# charliewatch-0402.net
KiCad netlist of a schematic drawn in EAGLE
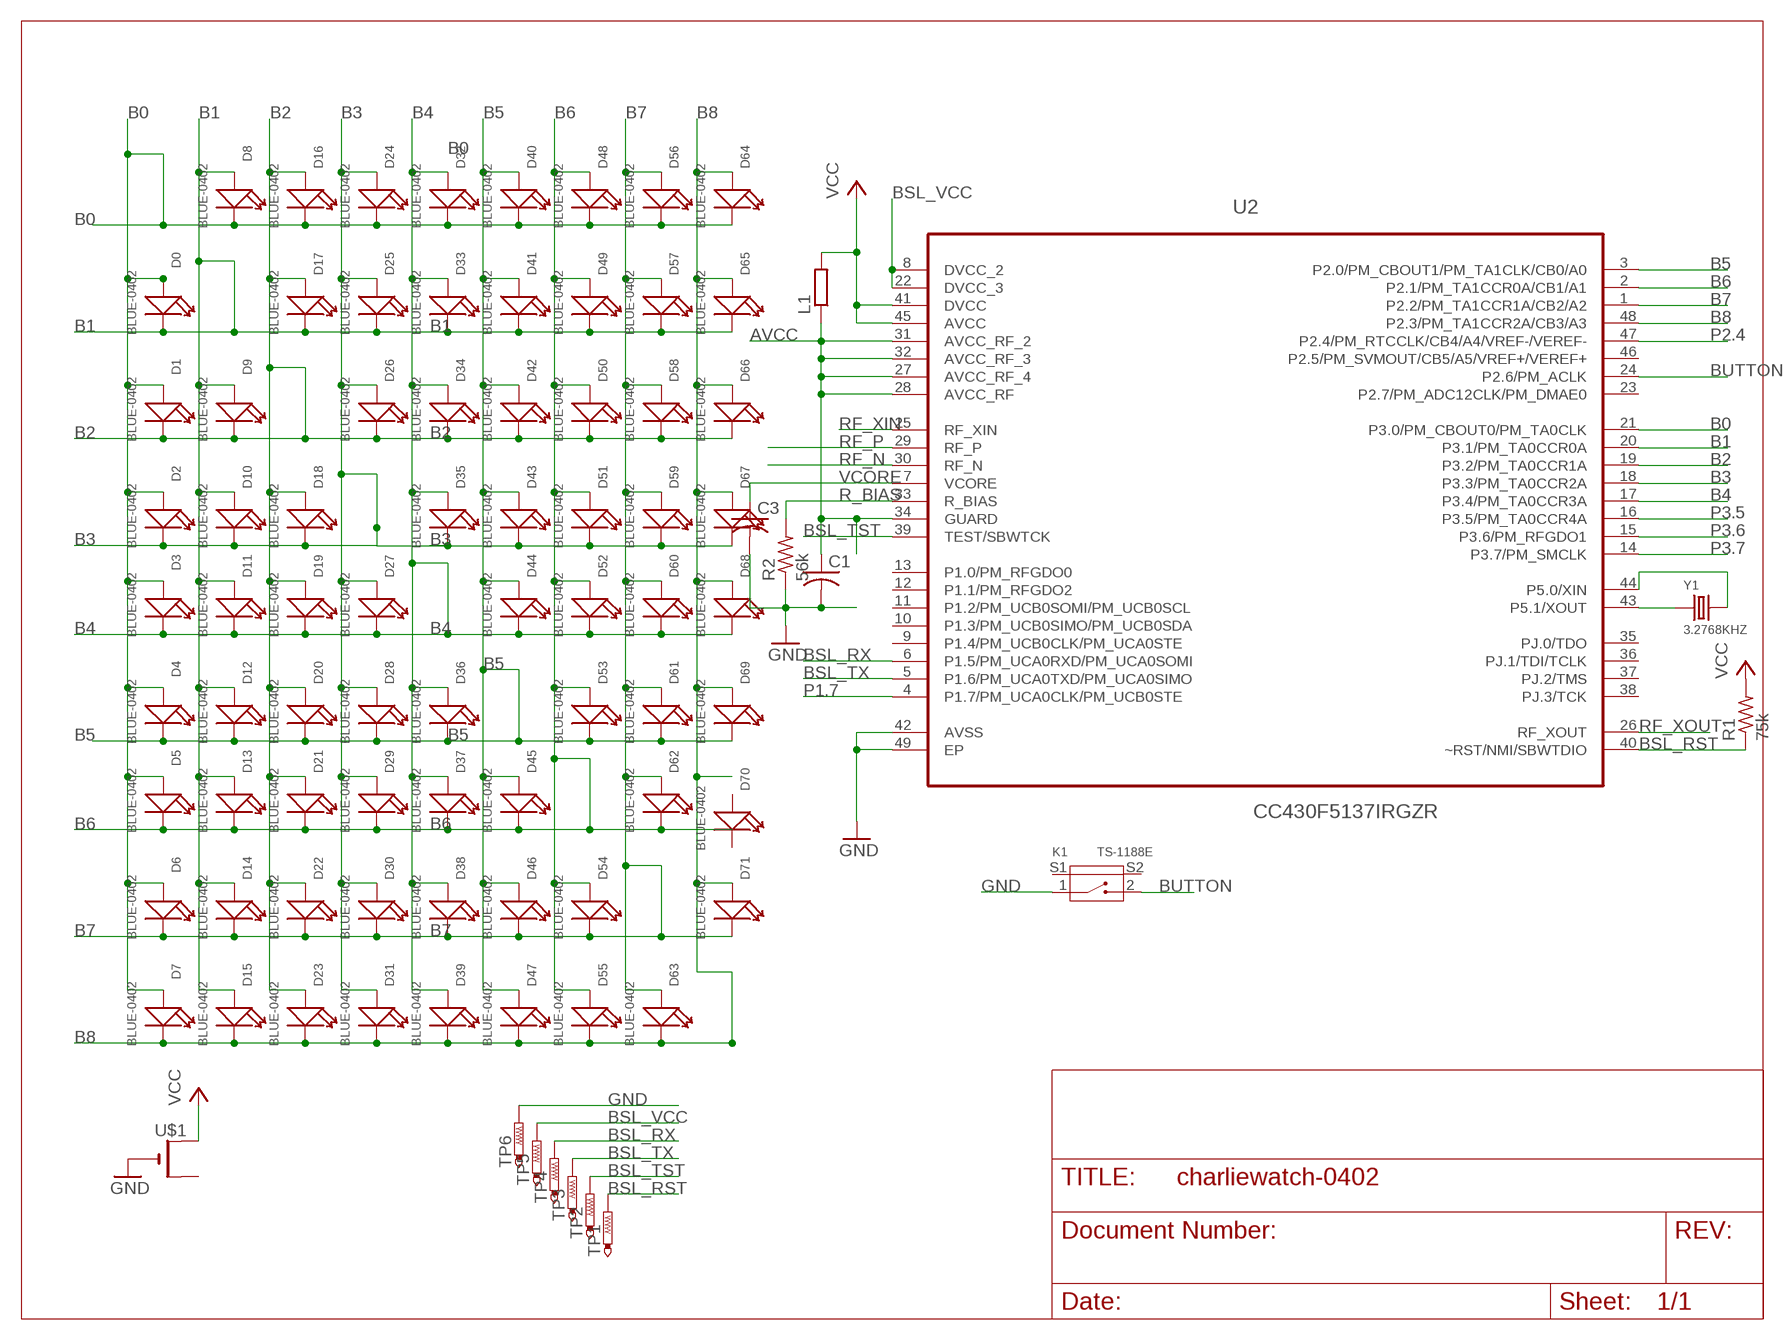
[diagram p0: schematic, sheet 1]

(export (version "E")
  (design (tool "Eeschema 10.0.6"))
  (components
    (comp (ref "C1")
      (value "C-USC0402")
      (footprint "eagle-import:C0402")
      (libsource (lib "eagle-import") (part "C-USC0402"))
    )
    (comp (ref "C3")
      (value "C-USC0402")
      (footprint "eagle-import:C0402")
      (libsource (lib "eagle-import") (part "C-USC0402"))
    )
    (comp (ref "D0")
      (value "BLUE-0402")
      (footprint "eagle-import:LED-0402")
      (fields (field (name "MPN") "BL-HB337A-AV-TRB"))
      (libsource (lib "eagle-import") (part "SMD-LED-CLEAR-BLUE(0402)"))
    )
    (comp (ref "D1")
      (value "BLUE-0402")
      (footprint "eagle-import:LED-0402")
      (fields (field (name "MPN") "BL-HB337A-AV-TRB"))
      (libsource (lib "eagle-import") (part "SMD-LED-CLEAR-BLUE(0402)"))
    )
    (comp (ref "D2")
      (value "BLUE-0402")
      (footprint "eagle-import:LED-0402")
      (fields (field (name "MPN") "BL-HB337A-AV-TRB"))
      (libsource (lib "eagle-import") (part "SMD-LED-CLEAR-BLUE(0402)"))
    )
    (comp (ref "D3")
      (value "BLUE-0402")
      (footprint "eagle-import:LED-0402")
      (fields (field (name "MPN") "BL-HB337A-AV-TRB"))
      (libsource (lib "eagle-import") (part "SMD-LED-CLEAR-BLUE(0402)"))
    )
    (comp (ref "D4")
      (value "BLUE-0402")
      (footprint "eagle-import:LED-0402")
      (fields (field (name "MPN") "BL-HB337A-AV-TRB"))
      (libsource (lib "eagle-import") (part "SMD-LED-CLEAR-BLUE(0402)"))
    )
    (comp (ref "D5")
      (value "BLUE-0402")
      (footprint "eagle-import:LED-0402")
      (fields (field (name "MPN") "BL-HB337A-AV-TRB"))
      (libsource (lib "eagle-import") (part "SMD-LED-CLEAR-BLUE(0402)"))
    )
    (comp (ref "D6")
      (value "BLUE-0402")
      (footprint "eagle-import:LED-0402")
      (fields (field (name "MPN") "BL-HB337A-AV-TRB"))
      (libsource (lib "eagle-import") (part "SMD-LED-CLEAR-BLUE(0402)"))
    )
    (comp (ref "D7")
      (value "BLUE-0402")
      (footprint "eagle-import:LED-0402")
      (fields (field (name "MPN") "BL-HB337A-AV-TRB"))
      (libsource (lib "eagle-import") (part "SMD-LED-CLEAR-BLUE(0402)"))
    )
    (comp (ref "D8")
      (value "BLUE-0402")
      (footprint "eagle-import:LED-0402")
      (fields (field (name "MPN") "BL-HB337A-AV-TRB"))
      (libsource (lib "eagle-import") (part "SMD-LED-CLEAR-BLUE(0402)"))
    )
    (comp (ref "D9")
      (value "BLUE-0402")
      (footprint "eagle-import:LED-0402")
      (fields (field (name "MPN") "BL-HB337A-AV-TRB"))
      (libsource (lib "eagle-import") (part "SMD-LED-CLEAR-BLUE(0402)"))
    )
    (comp (ref "D10")
      (value "BLUE-0402")
      (footprint "eagle-import:LED-0402")
      (fields (field (name "MPN") "BL-HB337A-AV-TRB"))
      (libsource (lib "eagle-import") (part "SMD-LED-CLEAR-BLUE(0402)"))
    )
    (comp (ref "D11")
      (value "BLUE-0402")
      (footprint "eagle-import:LED-0402")
      (fields (field (name "MPN") "BL-HB337A-AV-TRB"))
      (libsource (lib "eagle-import") (part "SMD-LED-CLEAR-BLUE(0402)"))
    )
    (comp (ref "D12")
      (value "BLUE-0402")
      (footprint "eagle-import:LED-0402")
      (fields (field (name "MPN") "BL-HB337A-AV-TRB"))
      (libsource (lib "eagle-import") (part "SMD-LED-CLEAR-BLUE(0402)"))
    )
    (comp (ref "D13")
      (value "BLUE-0402")
      (footprint "eagle-import:LED-0402")
      (fields (field (name "MPN") "BL-HB337A-AV-TRB"))
      (libsource (lib "eagle-import") (part "SMD-LED-CLEAR-BLUE(0402)"))
    )
    (comp (ref "D14")
      (value "BLUE-0402")
      (footprint "eagle-import:LED-0402")
      (fields (field (name "MPN") "BL-HB337A-AV-TRB"))
      (libsource (lib "eagle-import") (part "SMD-LED-CLEAR-BLUE(0402)"))
    )
    (comp (ref "D15")
      (value "BLUE-0402")
      (footprint "eagle-import:LED-0402")
      (fields (field (name "MPN") "BL-HB337A-AV-TRB"))
      (libsource (lib "eagle-import") (part "SMD-LED-CLEAR-BLUE(0402)"))
    )
    (comp (ref "D16")
      (value "BLUE-0402")
      (footprint "eagle-import:LED-0402")
      (fields (field (name "MPN") "BL-HB337A-AV-TRB"))
      (libsource (lib "eagle-import") (part "SMD-LED-CLEAR-BLUE(0402)"))
    )
    (comp (ref "D17")
      (value "BLUE-0402")
      (footprint "eagle-import:LED-0402")
      (fields (field (name "MPN") "BL-HB337A-AV-TRB"))
      (libsource (lib "eagle-import") (part "SMD-LED-CLEAR-BLUE(0402)"))
    )
    (comp (ref "D18")
      (value "BLUE-0402")
      (footprint "eagle-import:LED-0402")
      (fields (field (name "MPN") "BL-HB337A-AV-TRB"))
      (libsource (lib "eagle-import") (part "SMD-LED-CLEAR-BLUE(0402)"))
    )
    (comp (ref "D19")
      (value "BLUE-0402")
      (footprint "eagle-import:LED-0402")
      (fields (field (name "MPN") "BL-HB337A-AV-TRB"))
      (libsource (lib "eagle-import") (part "SMD-LED-CLEAR-BLUE(0402)"))
    )
    (comp (ref "D20")
      (value "BLUE-0402")
      (footprint "eagle-import:LED-0402")
      (fields (field (name "MPN") "BL-HB337A-AV-TRB"))
      (libsource (lib "eagle-import") (part "SMD-LED-CLEAR-BLUE(0402)"))
    )
    (comp (ref "D21")
      (value "BLUE-0402")
      (footprint "eagle-import:LED-0402")
      (fields (field (name "MPN") "BL-HB337A-AV-TRB"))
      (libsource (lib "eagle-import") (part "SMD-LED-CLEAR-BLUE(0402)"))
    )
    (comp (ref "D22")
      (value "BLUE-0402")
      (footprint "eagle-import:LED-0402")
      (fields (field (name "MPN") "BL-HB337A-AV-TRB"))
      (libsource (lib "eagle-import") (part "SMD-LED-CLEAR-BLUE(0402)"))
    )
    (comp (ref "D23")
      (value "BLUE-0402")
      (footprint "eagle-import:LED-0402")
      (fields (field (name "MPN") "BL-HB337A-AV-TRB"))
      (libsource (lib "eagle-import") (part "SMD-LED-CLEAR-BLUE(0402)"))
    )
    (comp (ref "D24")
      (value "BLUE-0402")
      (footprint "eagle-import:LED-0402")
      (fields (field (name "MPN") "BL-HB337A-AV-TRB"))
      (libsource (lib "eagle-import") (part "SMD-LED-CLEAR-BLUE(0402)"))
    )
    (comp (ref "D25")
      (value "BLUE-0402")
      (footprint "eagle-import:LED-0402")
      (fields (field (name "MPN") "BL-HB337A-AV-TRB"))
      (libsource (lib "eagle-import") (part "SMD-LED-CLEAR-BLUE(0402)"))
    )
    (comp (ref "D26")
      (value "BLUE-0402")
      (footprint "eagle-import:LED-0402")
      (fields (field (name "MPN") "BL-HB337A-AV-TRB"))
      (libsource (lib "eagle-import") (part "SMD-LED-CLEAR-BLUE(0402)"))
    )
    (comp (ref "D27")
      (value "BLUE-0402")
      (footprint "eagle-import:LED-0402")
      (fields (field (name "MPN") "BL-HB337A-AV-TRB"))
      (libsource (lib "eagle-import") (part "SMD-LED-CLEAR-BLUE(0402)"))
    )
    (comp (ref "D28")
      (value "BLUE-0402")
      (footprint "eagle-import:LED-0402")
      (fields (field (name "MPN") "BL-HB337A-AV-TRB"))
      (libsource (lib "eagle-import") (part "SMD-LED-CLEAR-BLUE(0402)"))
    )
    (comp (ref "D29")
      (value "BLUE-0402")
      (footprint "eagle-import:LED-0402")
      (fields (field (name "MPN") "BL-HB337A-AV-TRB"))
      (libsource (lib "eagle-import") (part "SMD-LED-CLEAR-BLUE(0402)"))
    )
    (comp (ref "D30")
      (value "BLUE-0402")
      (footprint "eagle-import:LED-0402")
      (fields (field (name "MPN") "BL-HB337A-AV-TRB"))
      (libsource (lib "eagle-import") (part "SMD-LED-CLEAR-BLUE(0402)"))
    )
    (comp (ref "D31")
      (value "BLUE-0402")
      (footprint "eagle-import:LED-0402")
      (fields (field (name "MPN") "BL-HB337A-AV-TRB"))
      (libsource (lib "eagle-import") (part "SMD-LED-CLEAR-BLUE(0402)"))
    )
    (comp (ref "D32")
      (value "BLUE-0402")
      (footprint "eagle-import:LED-0402")
      (fields (field (name "MPN") "BL-HB337A-AV-TRB"))
      (libsource (lib "eagle-import") (part "SMD-LED-CLEAR-BLUE(0402)"))
    )
    (comp (ref "D33")
      (value "BLUE-0402")
      (footprint "eagle-import:LED-0402")
      (fields (field (name "MPN") "BL-HB337A-AV-TRB"))
      (libsource (lib "eagle-import") (part "SMD-LED-CLEAR-BLUE(0402)"))
    )
    (comp (ref "D34")
      (value "BLUE-0402")
      (footprint "eagle-import:LED-0402")
      (fields (field (name "MPN") "BL-HB337A-AV-TRB"))
      (libsource (lib "eagle-import") (part "SMD-LED-CLEAR-BLUE(0402)"))
    )
    (comp (ref "D35")
      (value "BLUE-0402")
      (footprint "eagle-import:LED-0402")
      (fields (field (name "MPN") "BL-HB337A-AV-TRB"))
      (libsource (lib "eagle-import") (part "SMD-LED-CLEAR-BLUE(0402)"))
    )
    (comp (ref "D36")
      (value "BLUE-0402")
      (footprint "eagle-import:LED-0402")
      (fields (field (name "MPN") "BL-HB337A-AV-TRB"))
      (libsource (lib "eagle-import") (part "SMD-LED-CLEAR-BLUE(0402)"))
    )
    (comp (ref "D37")
      (value "BLUE-0402")
      (footprint "eagle-import:LED-0402")
      (fields (field (name "MPN") "BL-HB337A-AV-TRB"))
      (libsource (lib "eagle-import") (part "SMD-LED-CLEAR-BLUE(0402)"))
    )
    (comp (ref "D38")
      (value "BLUE-0402")
      (footprint "eagle-import:LED-0402")
      (fields (field (name "MPN") "BL-HB337A-AV-TRB"))
      (libsource (lib "eagle-import") (part "SMD-LED-CLEAR-BLUE(0402)"))
    )
    (comp (ref "D39")
      (value "BLUE-0402")
      (footprint "eagle-import:LED-0402")
      (fields (field (name "MPN") "BL-HB337A-AV-TRB"))
      (libsource (lib "eagle-import") (part "SMD-LED-CLEAR-BLUE(0402)"))
    )
    (comp (ref "D40")
      (value "BLUE-0402")
      (footprint "eagle-import:LED-0402")
      (fields (field (name "MPN") "BL-HB337A-AV-TRB"))
      (libsource (lib "eagle-import") (part "SMD-LED-CLEAR-BLUE(0402)"))
    )
    (comp (ref "D41")
      (value "BLUE-0402")
      (footprint "eagle-import:LED-0402")
      (fields (field (name "MPN") "BL-HB337A-AV-TRB"))
      (libsource (lib "eagle-import") (part "SMD-LED-CLEAR-BLUE(0402)"))
    )
    (comp (ref "D42")
      (value "BLUE-0402")
      (footprint "eagle-import:LED-0402")
      (fields (field (name "MPN") "BL-HB337A-AV-TRB"))
      (libsource (lib "eagle-import") (part "SMD-LED-CLEAR-BLUE(0402)"))
    )
    (comp (ref "D43")
      (value "BLUE-0402")
      (footprint "eagle-import:LED-0402")
      (fields (field (name "MPN") "BL-HB337A-AV-TRB"))
      (libsource (lib "eagle-import") (part "SMD-LED-CLEAR-BLUE(0402)"))
    )
    (comp (ref "D44")
      (value "BLUE-0402")
      (footprint "eagle-import:LED-0402")
      (fields (field (name "MPN") "BL-HB337A-AV-TRB"))
      (libsource (lib "eagle-import") (part "SMD-LED-CLEAR-BLUE(0402)"))
    )
    (comp (ref "D45")
      (value "BLUE-0402")
      (footprint "eagle-import:LED-0402")
      (fields (field (name "MPN") "BL-HB337A-AV-TRB"))
      (libsource (lib "eagle-import") (part "SMD-LED-CLEAR-BLUE(0402)"))
    )
    (comp (ref "D46")
      (value "BLUE-0402")
      (footprint "eagle-import:LED-0402")
      (fields (field (name "MPN") "BL-HB337A-AV-TRB"))
      (libsource (lib "eagle-import") (part "SMD-LED-CLEAR-BLUE(0402)"))
    )
    (comp (ref "D47")
      (value "BLUE-0402")
      (footprint "eagle-import:LED-0402")
      (fields (field (name "MPN") "BL-HB337A-AV-TRB"))
      (libsource (lib "eagle-import") (part "SMD-LED-CLEAR-BLUE(0402)"))
    )
    (comp (ref "D48")
      (value "BLUE-0402")
      (footprint "eagle-import:LED-0402")
      (fields (field (name "MPN") "BL-HB337A-AV-TRB"))
      (libsource (lib "eagle-import") (part "SMD-LED-CLEAR-BLUE(0402)"))
    )
    (comp (ref "D49")
      (value "BLUE-0402")
      (footprint "eagle-import:LED-0402")
      (fields (field (name "MPN") "BL-HB337A-AV-TRB"))
      (libsource (lib "eagle-import") (part "SMD-LED-CLEAR-BLUE(0402)"))
    )
    (comp (ref "D50")
      (value "BLUE-0402")
      (footprint "eagle-import:LED-0402")
      (fields (field (name "MPN") "BL-HB337A-AV-TRB"))
      (libsource (lib "eagle-import") (part "SMD-LED-CLEAR-BLUE(0402)"))
    )
    (comp (ref "D51")
      (value "BLUE-0402")
      (footprint "eagle-import:LED-0402")
      (fields (field (name "MPN") "BL-HB337A-AV-TRB"))
      (libsource (lib "eagle-import") (part "SMD-LED-CLEAR-BLUE(0402)"))
    )
    (comp (ref "D52")
      (value "BLUE-0402")
      (footprint "eagle-import:LED-0402")
      (fields (field (name "MPN") "BL-HB337A-AV-TRB"))
      (libsource (lib "eagle-import") (part "SMD-LED-CLEAR-BLUE(0402)"))
    )
    (comp (ref "D53")
      (value "BLUE-0402")
      (footprint "eagle-import:LED-0402")
      (fields (field (name "MPN") "BL-HB337A-AV-TRB"))
      (libsource (lib "eagle-import") (part "SMD-LED-CLEAR-BLUE(0402)"))
    )
    (comp (ref "D54")
      (value "BLUE-0402")
      (footprint "eagle-import:LED-0402")
      (fields (field (name "MPN") "BL-HB337A-AV-TRB"))
      (libsource (lib "eagle-import") (part "SMD-LED-CLEAR-BLUE(0402)"))
    )
    (comp (ref "D55")
      (value "BLUE-0402")
      (footprint "eagle-import:LED-0402")
      (fields (field (name "MPN") "BL-HB337A-AV-TRB"))
      (libsource (lib "eagle-import") (part "SMD-LED-CLEAR-BLUE(0402)"))
    )
    (comp (ref "D56")
      (value "BLUE-0402")
      (footprint "eagle-import:LED-0402")
      (fields (field (name "MPN") "BL-HB337A-AV-TRB"))
      (libsource (lib "eagle-import") (part "SMD-LED-CLEAR-BLUE(0402)"))
    )
    (comp (ref "D57")
      (value "BLUE-0402")
      (footprint "eagle-import:LED-0402")
      (fields (field (name "MPN") "BL-HB337A-AV-TRB"))
      (libsource (lib "eagle-import") (part "SMD-LED-CLEAR-BLUE(0402)"))
    )
    (comp (ref "D58")
      (value "BLUE-0402")
      (footprint "eagle-import:LED-0402")
      (fields (field (name "MPN") "BL-HB337A-AV-TRB"))
      (libsource (lib "eagle-import") (part "SMD-LED-CLEAR-BLUE(0402)"))
    )
    (comp (ref "D59")
      (value "BLUE-0402")
      (footprint "eagle-import:LED-0402")
      (fields (field (name "MPN") "BL-HB337A-AV-TRB"))
      (libsource (lib "eagle-import") (part "SMD-LED-CLEAR-BLUE(0402)"))
    )
    (comp (ref "D60")
      (value "BLUE-0402")
      (footprint "eagle-import:LED-0402")
      (fields (field (name "MPN") "BL-HB337A-AV-TRB"))
      (libsource (lib "eagle-import") (part "SMD-LED-CLEAR-BLUE(0402)"))
    )
    (comp (ref "D61")
      (value "BLUE-0402")
      (footprint "eagle-import:LED-0402")
      (fields (field (name "MPN") "BL-HB337A-AV-TRB"))
      (libsource (lib "eagle-import") (part "SMD-LED-CLEAR-BLUE(0402)"))
    )
    (comp (ref "D62")
      (value "BLUE-0402")
      (footprint "eagle-import:LED-0402")
      (fields (field (name "MPN") "BL-HB337A-AV-TRB"))
      (libsource (lib "eagle-import") (part "SMD-LED-CLEAR-BLUE(0402)"))
    )
    (comp (ref "D63")
      (value "BLUE-0402")
      (footprint "eagle-import:LED-0402")
      (fields (field (name "MPN") "BL-HB337A-AV-TRB"))
      (libsource (lib "eagle-import") (part "SMD-LED-CLEAR-BLUE(0402)"))
    )
    (comp (ref "D64")
      (value "BLUE-0402")
      (footprint "eagle-import:LED-0402")
      (fields (field (name "MPN") "BL-HB337A-AV-TRB"))
      (libsource (lib "eagle-import") (part "SMD-LED-CLEAR-BLUE(0402)"))
    )
    (comp (ref "D65")
      (value "BLUE-0402")
      (footprint "eagle-import:LED-0402")
      (fields (field (name "MPN") "BL-HB337A-AV-TRB"))
      (libsource (lib "eagle-import") (part "SMD-LED-CLEAR-BLUE(0402)"))
    )
    (comp (ref "D66")
      (value "BLUE-0402")
      (footprint "eagle-import:LED-0402")
      (fields (field (name "MPN") "BL-HB337A-AV-TRB"))
      (libsource (lib "eagle-import") (part "SMD-LED-CLEAR-BLUE(0402)"))
    )
    (comp (ref "D67")
      (value "BLUE-0402")
      (footprint "eagle-import:LED-0402")
      (fields (field (name "MPN") "BL-HB337A-AV-TRB"))
      (libsource (lib "eagle-import") (part "SMD-LED-CLEAR-BLUE(0402)"))
    )
    (comp (ref "D68")
      (value "BLUE-0402")
      (footprint "eagle-import:LED-0402")
      (fields (field (name "MPN") "BL-HB337A-AV-TRB"))
      (libsource (lib "eagle-import") (part "SMD-LED-CLEAR-BLUE(0402)"))
    )
    (comp (ref "D69")
      (value "BLUE-0402")
      (footprint "eagle-import:LED-0402")
      (fields (field (name "MPN") "BL-HB337A-AV-TRB"))
      (libsource (lib "eagle-import") (part "SMD-LED-CLEAR-BLUE(0402)"))
    )
    (comp (ref "D70")
      (value "BLUE-0402")
      (footprint "eagle-import:LED-0402")
      (fields (field (name "MPN") "BL-HB337A-AV-TRB"))
      (libsource (lib "eagle-import") (part "SMD-LED-CLEAR-BLUE(0402)"))
    )
    (comp (ref "D71")
      (value "BLUE-0402")
      (footprint "eagle-import:LED-0402")
      (fields (field (name "MPN") "BL-HB337A-AV-TRB"))
      (libsource (lib "eagle-import") (part "SMD-LED-CLEAR-BLUE(0402)"))
    )
    (comp (ref "K1")
      (value "TS-1188E")
      (footprint "eagle-import:SW4-SMD-7.0X3.5X3.5MM-90D")
      (libsource (lib "eagle-import") (part "SMD-BUTTON(2+2P-7X3.5MM-90D)"))
    )
    (comp (ref "L1")
      (value "R-EU_R0603")
      (footprint "eagle-import:R0603")
      (libsource (lib "eagle-import") (part "R-EU_R0603"))
    )
    (comp (ref "R1")
      (value "75k")
      (footprint "eagle-import:R0402")
      (libsource (lib "eagle-import") (part "R-US_R0402"))
    )
    (comp (ref "R2")
      (value "56k")
      (footprint "eagle-import:R0402")
      (libsource (lib "eagle-import") (part "R-US_R0402"))
    )
    (comp (ref "TP1")
      (value "PTR1TP10R")
      (footprint "eagle-import:TP10R")
      (libsource (lib "eagle-import") (part "PTR1TP10R"))
    )
    (comp (ref "TP2")
      (value "PTR1TP10R")
      (footprint "eagle-import:TP10R")
      (libsource (lib "eagle-import") (part "PTR1TP10R"))
    )
    (comp (ref "TP3")
      (value "PTR1TP10R")
      (footprint "eagle-import:TP10R")
      (libsource (lib "eagle-import") (part "PTR1TP10R"))
    )
    (comp (ref "TP4")
      (value "PTR1TP10R")
      (footprint "eagle-import:TP10R")
      (libsource (lib "eagle-import") (part "PTR1TP10R"))
    )
    (comp (ref "TP5")
      (value "PTR1TP10R")
      (footprint "eagle-import:TP10R")
      (libsource (lib "eagle-import") (part "PTR1TP10R"))
    )
    (comp (ref "TP6")
      (value "PTR1TP10SQ")
      (footprint "eagle-import:TP10SQ")
      (libsource (lib "eagle-import") (part "PTR1TP10SQ"))
    )
    (comp (ref "U$1")
      (value "CR2032SMT")
      (footprint "eagle-import:CR2032-SMD")
      (libsource (lib "eagle-import") (part "CR2032SMT"))
    )
    (comp (ref "U2")
      (value "CC430F5137IRGZR")
      (footprint "eagle-import:QFN50P700X700X100-49N")
      (libsource (lib "eagle-import") (part "CC430F5137IRGZR"))
    )
    (comp (ref "Y1")
      (value "3.2768KHZ")
      (footprint "eagle-import:X2-SMD-L2.0X1.2X0.55MM")
      (fields (field (name "MPN") "FC-12M"))
      (libsource (lib "eagle-import") (part "SMD-CRYSTAL-32.768KHZ-12.5PF-20PPM-90K(2P-L2.0X1.2MM)"))
    )
  )
  (nets
    (net (code "1") (name "/AVCC") (class "Default")
      (node (ref "C1") (pin "1") (pinfunction "1_1") (pintype "passive"))
      (node (ref "L1") (pin "1") (pinfunction "1_1") (pintype "passive"))
      (node (ref "U2") (pin "27") (pinfunction "AVCC_RF_4_27") (pintype "power_in"))
      (node (ref "U2") (pin "28") (pinfunction "AVCC_RF_28") (pintype "power_in"))
      (node (ref "U2") (pin "31") (pinfunction "AVCC_RF_2_31") (pintype "power_in"))
      (node (ref "U2") (pin "32") (pinfunction "AVCC_RF_3_32") (pintype "power_in"))
      (node (ref "U2") (pin "34") (pinfunction "GUARD_34") (pintype "input"))
    )
    (net (code "2") (name "/B0") (class "Default")
      (node (ref "D0") (pin "+") (pinfunction "+_+") (pintype "passive"))
      (node (ref "D1") (pin "+") (pinfunction "+_+") (pintype "passive"))
      (node (ref "D16") (pin "-") (pinfunction "-_-") (pintype "passive"))
      (node (ref "D2") (pin "+") (pinfunction "+_+") (pintype "passive"))
      (node (ref "D24") (pin "-") (pinfunction "-_-") (pintype "passive"))
      (node (ref "D3") (pin "+") (pinfunction "+_+") (pintype "passive"))
      (node (ref "D32") (pin "-") (pinfunction "-_-") (pintype "passive"))
      (node (ref "D4") (pin "+") (pinfunction "+_+") (pintype "passive"))
      (node (ref "D40") (pin "-") (pinfunction "-_-") (pintype "passive"))
      (node (ref "D48") (pin "-") (pinfunction "-_-") (pintype "passive"))
      (node (ref "D5") (pin "+") (pinfunction "+_+") (pintype "passive"))
      (node (ref "D56") (pin "-") (pinfunction "-_-") (pintype "passive"))
      (node (ref "D6") (pin "+") (pinfunction "+_+") (pintype "passive"))
      (node (ref "D64") (pin "-") (pinfunction "-_-") (pintype "passive"))
      (node (ref "D7") (pin "+") (pinfunction "+_+") (pintype "passive"))
      (node (ref "D8") (pin "-") (pinfunction "-_-") (pintype "passive"))
      (node (ref "U2") (pin "21") (pinfunction "P3.0/PM_CBOUT0/PM_TA0CLK_21") (pintype "bidirectional"))
    )
    (net (code "3") (name "/B1") (class "Default")
      (node (ref "D0") (pin "-") (pinfunction "-_-") (pintype "passive"))
      (node (ref "D10") (pin "+") (pinfunction "+_+") (pintype "passive"))
      (node (ref "D11") (pin "+") (pinfunction "+_+") (pintype "passive"))
      (node (ref "D12") (pin "+") (pinfunction "+_+") (pintype "passive"))
      (node (ref "D13") (pin "+") (pinfunction "+_+") (pintype "passive"))
      (node (ref "D14") (pin "+") (pinfunction "+_+") (pintype "passive"))
      (node (ref "D15") (pin "+") (pinfunction "+_+") (pintype "passive"))
      (node (ref "D17") (pin "-") (pinfunction "-_-") (pintype "passive"))
      (node (ref "D25") (pin "-") (pinfunction "-_-") (pintype "passive"))
      (node (ref "D33") (pin "-") (pinfunction "-_-") (pintype "passive"))
      (node (ref "D41") (pin "-") (pinfunction "-_-") (pintype "passive"))
      (node (ref "D49") (pin "-") (pinfunction "-_-") (pintype "passive"))
      (node (ref "D57") (pin "-") (pinfunction "-_-") (pintype "passive"))
      (node (ref "D65") (pin "-") (pinfunction "-_-") (pintype "passive"))
      (node (ref "D8") (pin "+") (pinfunction "+_+") (pintype "passive"))
      (node (ref "D9") (pin "+") (pinfunction "+_+") (pintype "passive"))
      (node (ref "U2") (pin "20") (pinfunction "P3.1/PM_TA0CCR0A_20") (pintype "bidirectional"))
    )
    (net (code "4") (name "/B2") (class "Default")
      (node (ref "D1") (pin "-") (pinfunction "-_-") (pintype "passive"))
      (node (ref "D16") (pin "+") (pinfunction "+_+") (pintype "passive"))
      (node (ref "D17") (pin "+") (pinfunction "+_+") (pintype "passive"))
      (node (ref "D18") (pin "+") (pinfunction "+_+") (pintype "passive"))
      (node (ref "D19") (pin "+") (pinfunction "+_+") (pintype "passive"))
      (node (ref "D20") (pin "+") (pinfunction "+_+") (pintype "passive"))
      (node (ref "D21") (pin "+") (pinfunction "+_+") (pintype "passive"))
      (node (ref "D22") (pin "+") (pinfunction "+_+") (pintype "passive"))
      (node (ref "D23") (pin "+") (pinfunction "+_+") (pintype "passive"))
      (node (ref "D26") (pin "-") (pinfunction "-_-") (pintype "passive"))
      (node (ref "D34") (pin "-") (pinfunction "-_-") (pintype "passive"))
      (node (ref "D42") (pin "-") (pinfunction "-_-") (pintype "passive"))
      (node (ref "D50") (pin "-") (pinfunction "-_-") (pintype "passive"))
      (node (ref "D58") (pin "-") (pinfunction "-_-") (pintype "passive"))
      (node (ref "D66") (pin "-") (pinfunction "-_-") (pintype "passive"))
      (node (ref "D9") (pin "-") (pinfunction "-_-") (pintype "passive"))
      (node (ref "U2") (pin "19") (pinfunction "P3.2/PM_TA0CCR1A_19") (pintype "bidirectional"))
    )
    (net (code "5") (name "/B3") (class "Default")
      (node (ref "D10") (pin "-") (pinfunction "-_-") (pintype "passive"))
      (node (ref "D18") (pin "-") (pinfunction "-_-") (pintype "passive"))
      (node (ref "D2") (pin "-") (pinfunction "-_-") (pintype "passive"))
      (node (ref "D24") (pin "+") (pinfunction "+_+") (pintype "passive"))
      (node (ref "D25") (pin "+") (pinfunction "+_+") (pintype "passive"))
      (node (ref "D26") (pin "+") (pinfunction "+_+") (pintype "passive"))
      (node (ref "D27") (pin "+") (pinfunction "+_+") (pintype "passive"))
      (node (ref "D28") (pin "+") (pinfunction "+_+") (pintype "passive"))
      (node (ref "D29") (pin "+") (pinfunction "+_+") (pintype "passive"))
      (node (ref "D30") (pin "+") (pinfunction "+_+") (pintype "passive"))
      (node (ref "D31") (pin "+") (pinfunction "+_+") (pintype "passive"))
      (node (ref "D35") (pin "-") (pinfunction "-_-") (pintype "passive"))
      (node (ref "D43") (pin "-") (pinfunction "-_-") (pintype "passive"))
      (node (ref "D51") (pin "-") (pinfunction "-_-") (pintype "passive"))
      (node (ref "D59") (pin "-") (pinfunction "-_-") (pintype "passive"))
      (node (ref "D67") (pin "-") (pinfunction "-_-") (pintype "passive"))
      (node (ref "U2") (pin "18") (pinfunction "P3.3/PM_TA0CCR2A_18") (pintype "bidirectional"))
    )
    (net (code "6") (name "/B4") (class "Default")
      (node (ref "D11") (pin "-") (pinfunction "-_-") (pintype "passive"))
      (node (ref "D19") (pin "-") (pinfunction "-_-") (pintype "passive"))
      (node (ref "D27") (pin "-") (pinfunction "-_-") (pintype "passive"))
      (node (ref "D3") (pin "-") (pinfunction "-_-") (pintype "passive"))
      (node (ref "D32") (pin "+") (pinfunction "+_+") (pintype "passive"))
      (node (ref "D33") (pin "+") (pinfunction "+_+") (pintype "passive"))
      (node (ref "D34") (pin "+") (pinfunction "+_+") (pintype "passive"))
      (node (ref "D35") (pin "+") (pinfunction "+_+") (pintype "passive"))
      (node (ref "D36") (pin "+") (pinfunction "+_+") (pintype "passive"))
      (node (ref "D37") (pin "+") (pinfunction "+_+") (pintype "passive"))
      (node (ref "D38") (pin "+") (pinfunction "+_+") (pintype "passive"))
      (node (ref "D39") (pin "+") (pinfunction "+_+") (pintype "passive"))
      (node (ref "D44") (pin "-") (pinfunction "-_-") (pintype "passive"))
      (node (ref "D52") (pin "-") (pinfunction "-_-") (pintype "passive"))
      (node (ref "D60") (pin "-") (pinfunction "-_-") (pintype "passive"))
      (node (ref "D68") (pin "-") (pinfunction "-_-") (pintype "passive"))
      (node (ref "U2") (pin "17") (pinfunction "P3.4/PM_TA0CCR3A_17") (pintype "bidirectional"))
    )
    (net (code "7") (name "/B5") (class "Default")
      (node (ref "D12") (pin "-") (pinfunction "-_-") (pintype "passive"))
      (node (ref "D20") (pin "-") (pinfunction "-_-") (pintype "passive"))
      (node (ref "D28") (pin "-") (pinfunction "-_-") (pintype "passive"))
      (node (ref "D36") (pin "-") (pinfunction "-_-") (pintype "passive"))
      (node (ref "D4") (pin "-") (pinfunction "-_-") (pintype "passive"))
      (node (ref "D40") (pin "+") (pinfunction "+_+") (pintype "passive"))
      (node (ref "D41") (pin "+") (pinfunction "+_+") (pintype "passive"))
      (node (ref "D42") (pin "+") (pinfunction "+_+") (pintype "passive"))
      (node (ref "D43") (pin "+") (pinfunction "+_+") (pintype "passive"))
      (node (ref "D44") (pin "+") (pinfunction "+_+") (pintype "passive"))
      (node (ref "D45") (pin "+") (pinfunction "+_+") (pintype "passive"))
      (node (ref "D46") (pin "+") (pinfunction "+_+") (pintype "passive"))
      (node (ref "D47") (pin "+") (pinfunction "+_+") (pintype "passive"))
      (node (ref "D53") (pin "-") (pinfunction "-_-") (pintype "passive"))
      (node (ref "D61") (pin "-") (pinfunction "-_-") (pintype "passive"))
      (node (ref "D69") (pin "-") (pinfunction "-_-") (pintype "passive"))
      (node (ref "U2") (pin "3") (pinfunction "P2.0/PM_CBOUT1/PM_TA1CLK/CB0/A0_3") (pintype "bidirectional"))
    )
    (net (code "8") (name "/B6") (class "Default")
      (node (ref "D13") (pin "-") (pinfunction "-_-") (pintype "passive"))
      (node (ref "D21") (pin "-") (pinfunction "-_-") (pintype "passive"))
      (node (ref "D29") (pin "-") (pinfunction "-_-") (pintype "passive"))
      (node (ref "D37") (pin "-") (pinfunction "-_-") (pintype "passive"))
      (node (ref "D45") (pin "-") (pinfunction "-_-") (pintype "passive"))
      (node (ref "D48") (pin "+") (pinfunction "+_+") (pintype "passive"))
      (node (ref "D49") (pin "+") (pinfunction "+_+") (pintype "passive"))
      (node (ref "D5") (pin "-") (pinfunction "-_-") (pintype "passive"))
      (node (ref "D50") (pin "+") (pinfunction "+_+") (pintype "passive"))
      (node (ref "D51") (pin "+") (pinfunction "+_+") (pintype "passive"))
      (node (ref "D52") (pin "+") (pinfunction "+_+") (pintype "passive"))
      (node (ref "D53") (pin "+") (pinfunction "+_+") (pintype "passive"))
      (node (ref "D54") (pin "+") (pinfunction "+_+") (pintype "passive"))
      (node (ref "D55") (pin "+") (pinfunction "+_+") (pintype "passive"))
      (node (ref "D62") (pin "-") (pinfunction "-_-") (pintype "passive"))
      (node (ref "U2") (pin "2") (pinfunction "P2.1/PM_TA1CCR0A/CB1/A1_2") (pintype "bidirectional"))
    )
    (net (code "9") (name "/B7") (class "Default")
      (node (ref "D14") (pin "-") (pinfunction "-_-") (pintype "passive"))
      (node (ref "D22") (pin "-") (pinfunction "-_-") (pintype "passive"))
      (node (ref "D30") (pin "-") (pinfunction "-_-") (pintype "passive"))
      (node (ref "D38") (pin "-") (pinfunction "-_-") (pintype "passive"))
      (node (ref "D46") (pin "-") (pinfunction "-_-") (pintype "passive"))
      (node (ref "D54") (pin "-") (pinfunction "-_-") (pintype "passive"))
      (node (ref "D56") (pin "+") (pinfunction "+_+") (pintype "passive"))
      (node (ref "D57") (pin "+") (pinfunction "+_+") (pintype "passive"))
      (node (ref "D58") (pin "+") (pinfunction "+_+") (pintype "passive"))
      (node (ref "D59") (pin "+") (pinfunction "+_+") (pintype "passive"))
      (node (ref "D6") (pin "-") (pinfunction "-_-") (pintype "passive"))
      (node (ref "D60") (pin "+") (pinfunction "+_+") (pintype "passive"))
      (node (ref "D61") (pin "+") (pinfunction "+_+") (pintype "passive"))
      (node (ref "D62") (pin "+") (pinfunction "+_+") (pintype "passive"))
      (node (ref "D63") (pin "+") (pinfunction "+_+") (pintype "passive"))
      (node (ref "D71") (pin "-") (pinfunction "-_-") (pintype "passive"))
      (node (ref "U2") (pin "1") (pinfunction "P2.2/PM_TA1CCR1A/CB2/A2_1") (pintype "bidirectional"))
    )
    (net (code "10") (name "/B8") (class "Default")
      (node (ref "D15") (pin "-") (pinfunction "-_-") (pintype "passive"))
      (node (ref "D23") (pin "-") (pinfunction "-_-") (pintype "passive"))
      (node (ref "D31") (pin "-") (pinfunction "-_-") (pintype "passive"))
      (node (ref "D39") (pin "-") (pinfunction "-_-") (pintype "passive"))
      (node (ref "D47") (pin "-") (pinfunction "-_-") (pintype "passive"))
      (node (ref "D55") (pin "-") (pinfunction "-_-") (pintype "passive"))
      (node (ref "D63") (pin "-") (pinfunction "-_-") (pintype "passive"))
      (node (ref "D64") (pin "+") (pinfunction "+_+") (pintype "passive"))
      (node (ref "D65") (pin "+") (pinfunction "+_+") (pintype "passive"))
      (node (ref "D66") (pin "+") (pinfunction "+_+") (pintype "passive"))
      (node (ref "D67") (pin "+") (pinfunction "+_+") (pintype "passive"))
      (node (ref "D68") (pin "+") (pinfunction "+_+") (pintype "passive"))
      (node (ref "D69") (pin "+") (pinfunction "+_+") (pintype "passive"))
      (node (ref "D7") (pin "-") (pinfunction "-_-") (pintype "passive"))
      (node (ref "D71") (pin "+") (pinfunction "+_+") (pintype "passive"))
      (node (ref "U2") (pin "48") (pinfunction "P2.3/PM_TA1CCR2A/CB3/A3_48") (pintype "bidirectional"))
    )
    (net (code "11") (name "/BSL_RST") (class "Default")
      (node (ref "R1") (pin "1") (pinfunction "1_1") (pintype "passive"))
      (node (ref "TP1") (pin "TP") (pinfunction "TP_TP") (pintype "input"))
      (node (ref "U2") (pin "40") (pinfunction "~{RST/NMI/SBWTDIO}_40") (pintype "bidirectional"))
    )
    (net (code "12") (name "/BSL_RX") (class "Default")
      (node (ref "TP4") (pin "TP") (pinfunction "TP_TP") (pintype "input"))
      (node (ref "U2") (pin "6") (pinfunction "P1.5/PM_UCA0RXD/PM_UCA0SOMI_6") (pintype "bidirectional"))
    )
    (net (code "13") (name "/BSL_TST") (class "Default")
      (node (ref "TP2") (pin "TP") (pinfunction "TP_TP") (pintype "input"))
      (node (ref "U2") (pin "39") (pinfunction "TEST/SBWTCK_39") (pintype "input"))
    )
    (net (code "14") (name "/BSL_TX") (class "Default")
      (node (ref "TP3") (pin "TP") (pinfunction "TP_TP") (pintype "input"))
      (node (ref "U2") (pin "5") (pinfunction "P1.6/PM_UCA0TXD/PM_UCA0SIMO_5") (pintype "bidirectional"))
    )
    (net (code "15") (name "/BSL_VCC") (class "Default")
      (node (ref "TP5") (pin "TP") (pinfunction "TP_TP") (pintype "input"))
      (node (ref "U2") (pin "22") (pinfunction "DVCC_3_22") (pintype "power_in"))
      (node (ref "U2") (pin "8") (pinfunction "DVCC_2_8") (pintype "power_in"))
    )
    (net (code "16") (name "/BUTTON") (class "Default")
      (node (ref "K1") (pin "2") (pinfunction "2_2") (pintype "bidirectional"))
      (node (ref "U2") (pin "24") (pinfunction "P2.6/PM_ACLK_24") (pintype "bidirectional"))
    )
    (net (code "17") (name "/P1.7") (class "Default")
      (node (ref "U2") (pin "4") (pinfunction "P1.7/PM_UCA0CLK/PM_UCB0STE_4") (pintype "bidirectional"))
    )
    (net (code "18") (name "/P2.4") (class "Default")
      (node (ref "U2") (pin "47") (pinfunction "P2.4/PM_RTCCLK/CB4/A4/VREF-/VEREF-_47") (pintype "bidirectional"))
    )
    (net (code "19") (name "/P3.5") (class "Default")
      (node (ref "U2") (pin "16") (pinfunction "P3.5/PM_TA0CCR4A_16") (pintype "bidirectional"))
    )
    (net (code "20") (name "/P3.6") (class "Default")
      (node (ref "U2") (pin "15") (pinfunction "P3.6/PM_RFGDO1_15") (pintype "bidirectional"))
    )
    (net (code "21") (name "/P3.7") (class "Default")
      (node (ref "U2") (pin "14") (pinfunction "P3.7/PM_SMCLK_14") (pintype "bidirectional"))
    )
    (net (code "22") (name "/RF_N") (class "Default")
      (node (ref "U2") (pin "30") (pinfunction "RF_N_30") (pintype "bidirectional"))
    )
    (net (code "23") (name "/RF_P") (class "Default")
      (node (ref "U2") (pin "29") (pinfunction "RF_P_29") (pintype "bidirectional"))
    )
    (net (code "24") (name "/RF_XIN") (class "Default")
      (node (ref "U2") (pin "25") (pinfunction "RF_XIN_25") (pintype "input"))
    )
    (net (code "25") (name "/RF_XOUT") (class "Default")
      (node (ref "U2") (pin "26") (pinfunction "RF_XOUT_26") (pintype "output"))
    )
    (net (code "26") (name "/R_BIAS") (class "Default")
      (node (ref "R2") (pin "2") (pinfunction "2_2") (pintype "passive"))
      (node (ref "U2") (pin "33") (pinfunction "R_BIAS_33") (pintype "input"))
    )
    (net (code "27") (name "/VCORE") (class "Default")
      (node (ref "C3") (pin "1") (pinfunction "1_1") (pintype "passive"))
      (node (ref "U2") (pin "7") (pinfunction "VCORE_7") (pintype "input"))
    )
    (net (code "28") (name "GND") (class "Default")
      (node (ref "C1") (pin "2") (pinfunction "2_2") (pintype "passive"))
      (node (ref "C3") (pin "2") (pinfunction "2_2") (pintype "passive"))
      (node (ref "K1") (pin "1") (pinfunction "1_1") (pintype "bidirectional"))
      (node (ref "R2") (pin "1") (pinfunction "1_1") (pintype "passive"))
      (node (ref "TP6") (pin "TP") (pinfunction "TP_TP") (pintype "input"))
      (node (ref "U$1") (pin "-") (pinfunction "-_-") (pintype "passive"))
      (node (ref "U2") (pin "42") (pinfunction "AVSS_42") (pintype "passive"))
      (node (ref "U2") (pin "49") (pinfunction "EP_49") (pintype "passive"))
    )
    (net (code "29") (name "Net-(U2-P5.0{slash}XIN)") (class "Default")
      (node (ref "U2") (pin "44") (pinfunction "P5.0/XIN_44") (pintype "bidirectional"))
      (node (ref "Y1") (pin "2") (pinfunction "2_2") (pintype "passive"))
    )
    (net (code "30") (name "Net-(U2-P5.1{slash}XOUT)") (class "Default")
      (node (ref "U2") (pin "43") (pinfunction "P5.1/XOUT_43") (pintype "bidirectional"))
      (node (ref "Y1") (pin "1") (pinfunction "1_1") (pintype "passive"))
    )
    (net (code "31") (name "VCC") (class "Default")
      (node (ref "L1") (pin "2") (pinfunction "2_2") (pintype "passive"))
      (node (ref "R1") (pin "2") (pinfunction "2_2") (pintype "passive"))
      (node (ref "U$1") (pin "+$1") (pinfunction "+_+$1") (pintype "passive"))
      (node (ref "U2") (pin "41") (pinfunction "DVCC_41") (pintype "power_in"))
      (node (ref "U2") (pin "45") (pinfunction "AVCC_45") (pintype "power_in"))
    )
    (net (code "32") (name "unconnected-(D70-Pad+)") (class "Default")
      (node (ref "D70") (pin "+") (pinfunction "+_+") (pintype "passive"))
    )
    (net (code "33") (name "unconnected-(D70-Pad-)") (class "Default")
      (node (ref "D70") (pin "-") (pinfunction "-_-") (pintype "passive"))
    )
    (net (code "34") (name "unconnected-(K1-PadS1)") (class "Default")
      (node (ref "K1") (pin "S1") (pinfunction "S1_S1") (pintype "bidirectional"))
    )
    (net (code "35") (name "unconnected-(K1-PadS2)") (class "Default")
      (node (ref "K1") (pin "S2") (pinfunction "S2_S2") (pintype "bidirectional"))
    )
    (net (code "36") (name "unconnected-(U$1-+1-Pad+$2)") (class "Default")
      (node (ref "U$1") (pin "+$2") (pinfunction "+1_+$2") (pintype "passive"))
    )
    (net (code "37") (name "unconnected-(U2-P1.0{slash}PM_RFGDO0-Pad13)") (class "Default")
      (node (ref "U2") (pin "13") (pinfunction "P1.0/PM_RFGDO0_13") (pintype "bidirectional"))
    )
    (net (code "38") (name "unconnected-(U2-P1.1{slash}PM_RFGDO2-Pad12)") (class "Default")
      (node (ref "U2") (pin "12") (pinfunction "P1.1/PM_RFGDO2_12") (pintype "bidirectional"))
    )
    (net (code "39") (name "unconnected-(U2-P1.2{slash}PM_UCB0SOMI{slash}PM_UCB0SCL-Pad11)") (class "Default")
      (node (ref "U2") (pin "11") (pinfunction "P1.2/PM_UCB0SOMI/PM_UCB0SCL_11") (pintype "bidirectional"))
    )
    (net (code "40") (name "unconnected-(U2-P1.3{slash}PM_UCB0SIMO{slash}PM_UCB0SDA-Pad10)") (class "Default")
      (node (ref "U2") (pin "10") (pinfunction "P1.3/PM_UCB0SIMO/PM_UCB0SDA_10") (pintype "bidirectional"))
    )
    (net (code "41") (name "unconnected-(U2-P1.4{slash}PM_UCB0CLK{slash}PM_UCA0STE-Pad9)") (class "Default")
      (node (ref "U2") (pin "9") (pinfunction "P1.4/PM_UCB0CLK/PM_UCA0STE_9") (pintype "bidirectional"))
    )
    (net (code "42") (name "unconnected-(U2-P2.5{slash}PM_SVMOUT{slash}CB5{slash}A5{slash}VREF+{slash}VEREF+-Pad46)") (class "Default")
      (node (ref "U2") (pin "46") (pinfunction "P2.5/PM_SVMOUT/CB5/A5/VREF+/VEREF+_46") (pintype "bidirectional"))
    )
    (net (code "43") (name "unconnected-(U2-P2.7{slash}PM_ADC12CLK{slash}PM_DMAE0-Pad23)") (class "Default")
      (node (ref "U2") (pin "23") (pinfunction "P2.7/PM_ADC12CLK/PM_DMAE0_23") (pintype "bidirectional"))
    )
    (net (code "44") (name "unconnected-(U2-PJ.0{slash}TDO-Pad35)") (class "Default")
      (node (ref "U2") (pin "35") (pinfunction "PJ.0/TDO_35") (pintype "bidirectional"))
    )
    (net (code "45") (name "unconnected-(U2-PJ.1{slash}TDI{slash}TCLK-Pad36)") (class "Default")
      (node (ref "U2") (pin "36") (pinfunction "PJ.1/TDI/TCLK_36") (pintype "bidirectional"))
    )
    (net (code "46") (name "unconnected-(U2-PJ.2{slash}TMS-Pad37)") (class "Default")
      (node (ref "U2") (pin "37") (pinfunction "PJ.2/TMS_37") (pintype "bidirectional"))
    )
    (net (code "47") (name "unconnected-(U2-PJ.3{slash}TCK-Pad38)") (class "Default")
      (node (ref "U2") (pin "38") (pinfunction "PJ.3/TCK_38") (pintype "bidirectional"))
    )
  )
)
